# Db_psu_1v2_2v5.net
KiCad netlist of a schematic drawn in Altium Designer
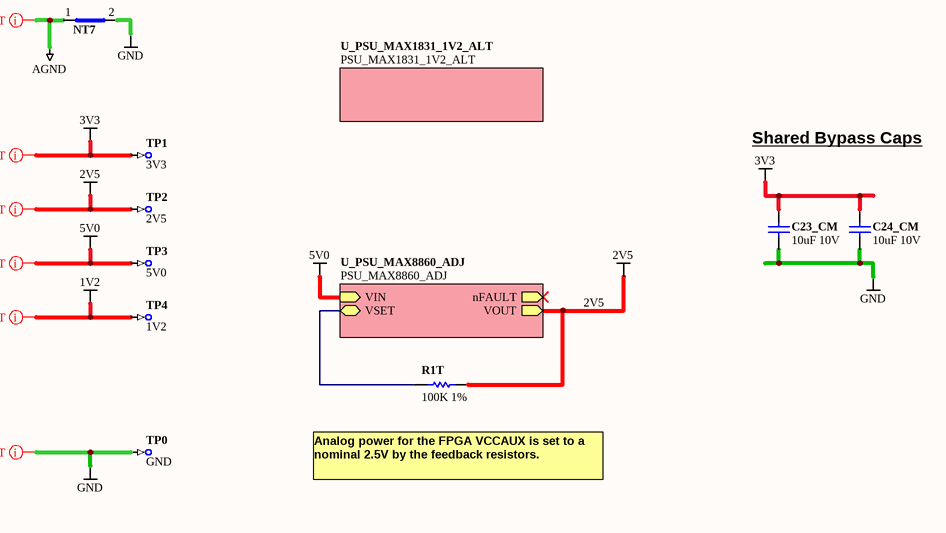
[diagram p0: Db_psu_1v2_2v5.schdoc]

(export (version "E")
  (design (tool "Eeschema 10.0.6"))
  (components
    (comp (ref "C23_CM")
      (value "10uF 10V")
      (footprint "CAPC2012-STAR")
      (description "Capacitor, Ceramic, 10uF 10% 10V 0805 (2012) X5R")
      (fields (field (name "TOLERANCE") "10 %"))
      (libsource (lib "AltiumDesignLibrary") (part "CAP-NP"))
    )
    (comp (ref "C24_CM")
      (value "10uF 10V")
      (footprint "CAPC2012-STAR")
      (description "Capacitor, Ceramic, 10uF 10% 10V 0805 (2012) X5R")
      (fields (field (name "TOLERANCE") "10 %"))
      (libsource (lib "AltiumDesignLibrary") (part "CAP-NP"))
    )
    (comp (ref "NT7")
      (value "Net Tie SMT2")
      (footprint "NETTIE-SMT2-8X8")
      (description "Net-Tie, Surface Mount, 2 x 0.4mm x 0.2mm SMT Pads - For 0.2mm Track")
      (libsource (lib "AltiumDesignLibrary") (part "NETTIE-SMT2"))
    )
    (comp (ref "R1T")
      (value "100K 1%")
      (footprint "RESC1005-STAR")
      (description "Resistor, 100K 1% 0402 (1005)")
      (fields (field (name "TOLERANCE") "1 %"))
      (libsource (lib "AltiumDesignLibrary") (part "RES"))
    )
    (comp (ref "TP0")
      (value "GND")
      (footprint "TestPin")
      (description "Test Point, PCB Mount with Silkscreen Box")
      (libsource (lib "AltiumDesignLibrary") (part "TestPin"))
    )
    (comp (ref "TP1")
      (value "3V3")
      (footprint "TestPin")
      (description "Test Point, PCB Mount with Silkscreen Box")
      (libsource (lib "AltiumDesignLibrary") (part "TestPin"))
    )
    (comp (ref "TP2")
      (value "2V5")
      (footprint "TestPin")
      (description "Test Point, PCB Mount with Silkscreen Box")
      (libsource (lib "AltiumDesignLibrary") (part "TestPin"))
    )
    (comp (ref "TP3")
      (value "5V0")
      (footprint "TestPin")
      (description "Test Point, PCB Mount with Silkscreen Box")
      (libsource (lib "AltiumDesignLibrary") (part "TestPin"))
    )
    (comp (ref "TP4")
      (value "1V2")
      (footprint "TestPin")
      (description "Test Point, PCB Mount with Silkscreen Box")
      (libsource (lib "AltiumDesignLibrary") (part "TestPin"))
    )
  )
  (nets
    (net (code "1") (name "/VSET") (class "Default")
      (node (ref "R1T") (pin "1") (pinfunction "1_1") (pintype "passive"))
    )
    (net (code "3") (name "1V2") (class "Default")
      (node (ref "TP4") (pin "1") (pinfunction "1_1") (pintype "input"))
    )
    (net (code "4") (name "2V5") (class "Default")
      (node (ref "R1T") (pin "2") (pinfunction "2_2") (pintype "passive"))
      (node (ref "TP2") (pin "1") (pinfunction "1_1") (pintype "input"))
    )
    (net (code "5") (name "3V3") (class "Default")
      (node (ref "C23_CM") (pin "1") (pinfunction "1_1") (pintype "passive"))
      (node (ref "C24_CM") (pin "1") (pinfunction "1_1") (pintype "passive"))
      (node (ref "TP1") (pin "1") (pinfunction "1_1") (pintype "input"))
    )
    (net (code "6") (name "5V0") (class "Default")
      (node (ref "TP3") (pin "1") (pinfunction "1_1") (pintype "input"))
    )
    (net (code "7") (name "AGND") (class "Default")
      (node (ref "NT7") (pin "1") (pinfunction "Net1_1") (pintype "passive"))
    )
    (net (code "8") (name "GND") (class "Default")
      (node (ref "C23_CM") (pin "2") (pinfunction "2_2") (pintype "passive"))
      (node (ref "C24_CM") (pin "2") (pinfunction "2_2") (pintype "passive"))
      (node (ref "NT7") (pin "2") (pinfunction "Net2_2") (pintype "passive"))
      (node (ref "TP0") (pin "1") (pinfunction "1_1") (pintype "input"))
    )
  )
)
